# Power.net
KiCad netlist of a schematic drawn in Altium Designer
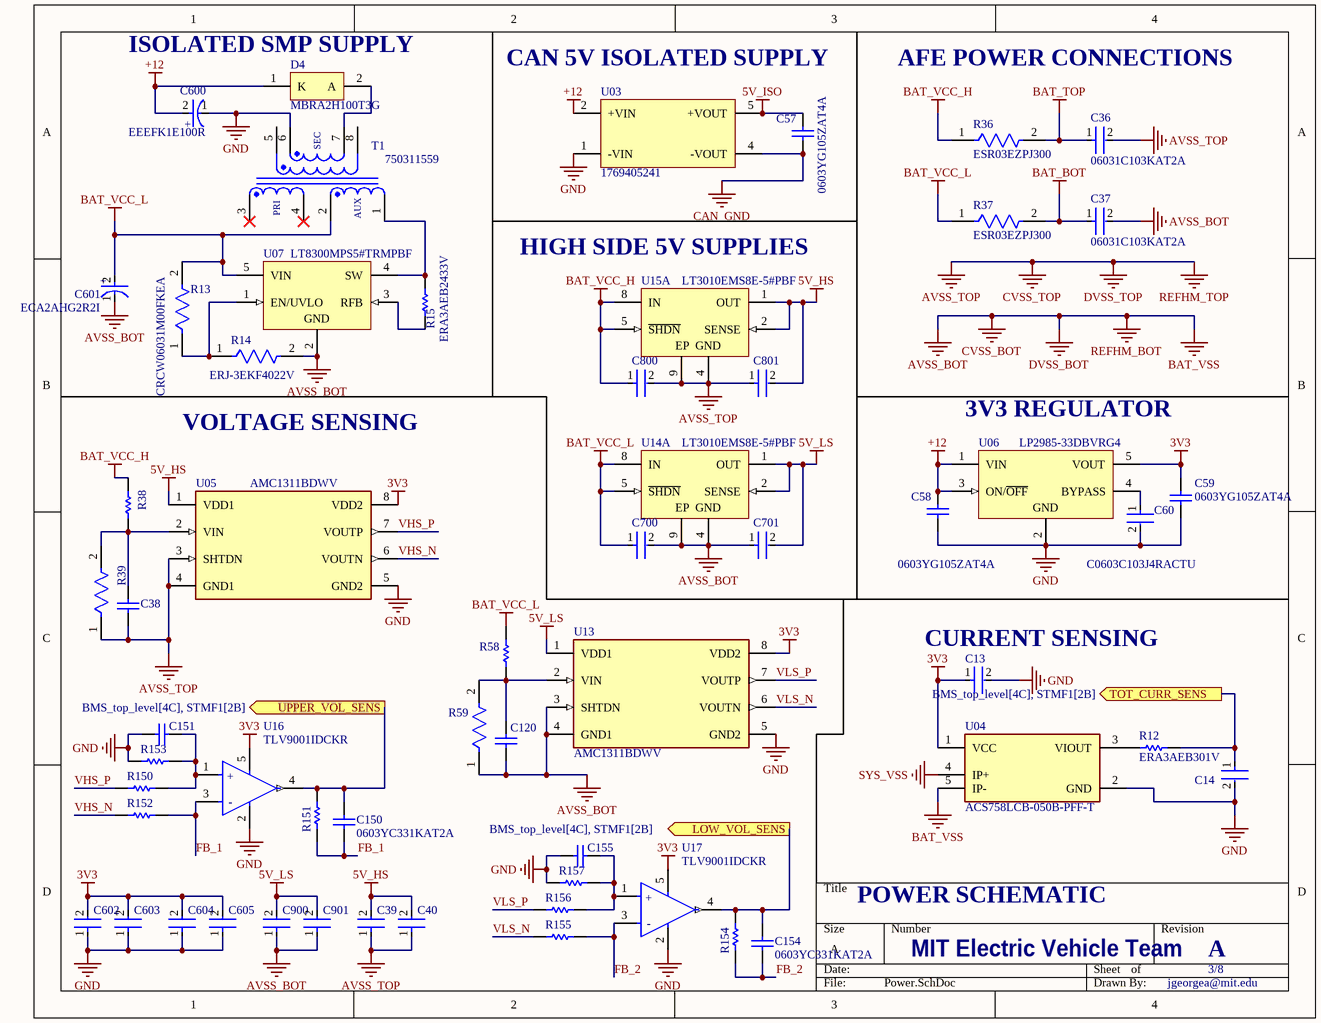
[diagram p0: Power.SchDoc]

(export (version "E")
  (design (tool "Eeschema 10.0.6"))
  (components
    (comp (ref "C13")
      (value "CGA3E2X7R1H104K080AA")
      (footprint "FP-CGA3E-0_3-0_1-IPC_A")
      (description "Cap Ceramic 100nF 50V X7R 10% Pad SMD 0603 +125°C Automotive T/R")
      (fields (field (name "TOLERANCE") "10%") (field (name "VOLTAGE") "50V"))
      (libsource (lib "Altium Content Vault") (part "b4654b650e69147ec39a6b967a45e02"))
    )
    (comp (ref "C14")
      (value "CGA3E2X7R1H104K080AA")
      (footprint "FP-CGA3E-0_3-0_1-IPC_A")
      (description "Cap Ceramic 100nF 50V X7R 10% Pad SMD 0603 +125°C Automotive T/R")
      (fields (field (name "TOLERANCE") "10%") (field (name "VOLTAGE") "50V"))
      (libsource (lib "Altium Content Vault") (part "b4654b650e69147ec39a6b967a45e02"))
    )
    (comp (ref "C36")
      (value "06031C103KAT2A")
      (footprint "FP-0603-L_1_6_0_15-W_0_81-IPC_C")
      (description "General Purpose Ceramic Capacitor, 0603, 10nF, 10%, X7R, 15%, 100V")
      (fields (field (name "VOLTAGE") "100V") (field (name "TOLERANCE") "10%"))
      (libsource (lib "Altium Content Vault") (part "02cd4be3c70576c341d710602a673aa"))
    )
    (comp (ref "C37")
      (value "06031C103KAT2A")
      (footprint "FP-0603-L_1_6_0_15-W_0_81-IPC_C")
      (description "General Purpose Ceramic Capacitor, 0603, 10nF, 10%, X7R, 15%, 100V")
      (fields (field (name "VOLTAGE") "100V") (field (name "TOLERANCE") "10%"))
      (libsource (lib "Altium Content Vault") (part "02cd4be3c70576c341d710602a673aa"))
    )
    (comp (ref "C38")
      (value "CC0603JRNPO9BN101")
      (footprint "CAPC1608X90X40ML10T20")
      (description "Chip Capacitor, 100 pF, +/- 5%, 50 V, -55 to 125 degC, 0603 (1608 Metric), RoHS, Tape and Reel")
      (fields (field (name "TOLERANCE") "5%") (field (name "VOLTAGE") "50V"))
      (libsource (lib "Altium Content Vault") (part "CAP-NP-2"))
    )
    (comp (ref "C39")
      (value "C2012X7S2A105K125AE")
      (footprint "FP-C2012-125-IPC_B")
      (description "CAP CER 1UF 100V X7S 0805")
      (fields (field (name "TOLERANCE") "10%"))
      (libsource (lib "Altium Content Vault") (part "02cd4be3c70576c341d710602a673aa"))
    )
    (comp (ref "C40")
      (value "CGA3E2X7R1H104K080AA")
      (footprint "FP-CGA3E-0_3-0_1-IPC_A")
      (description "Cap Ceramic 100nF 50V X7R 10% Pad SMD 0603 +125°C Automotive T/R")
      (fields (field (name "TOLERANCE") "10%") (field (name "VOLTAGE") "50V"))
      (libsource (lib "Altium Content Vault") (part "b4654b650e69147ec39a6b967a45e02"))
    )
    (comp (ref "C57")
      (value "0603YG105ZAT4A")
      (footprint "CAPC1608X90X35ML15T15")
      (fields (field (name "MANUFACTURER") "AVX Interconnect / Elco"))
      (libsource (lib "Altium Content Vault") (part "CAP"))
    )
    (comp (ref "C58")
      (value "0603YG105ZAT4A")
      (footprint "CAPC1608X90X35ML15T15")
      (fields (field (name "MANUFACTURER") "AVX Interconnect / Elco"))
      (libsource (lib "Altium Content Vault") (part "CAP"))
    )
    (comp (ref "C59")
      (value "0603YG105ZAT4A")
      (footprint "CAPC1608X90X35ML15T15")
      (fields (field (name "MANUFACTURER") "AVX Interconnect / Elco"))
      (libsource (lib "Altium Content Vault") (part "CAP"))
    )
    (comp (ref "C60")
      (value "C0603C103J4RACTU")
      (footprint "FP-C0603C-CF-MFG")
      (description "CAP CER 10000PF 16V 5% X7R 0603")
      (fields (field (name "TOLERANCE") "0.05") (field (name "MANUFACTURER") "KEMET"))
      (libsource (lib "Altium Content Vault") (part "b4654b650e69147ec39a6b967a45e02"))
    )
    (comp (ref "C120")
      (value "CC0603JRNPO9BN101")
      (footprint "CAPC1608X90X40ML10T20")
      (description "Chip Capacitor, 100 pF, +/- 5%, 50 V, -55 to 125 degC, 0603 (1608 Metric), RoHS, Tape and Reel")
      (fields (field (name "TOLERANCE") "5%") (field (name "VOLTAGE") "50V"))
      (libsource (lib "Altium Content Vault") (part "CAP-NP-2"))
    )
    (comp (ref "C150")
      (value "0603YC331KAT2A")
      (footprint "CAPC1608X90X35ML15T15")
      (fields (field (name "MANUFACTURER") "AVX Interconnect / Elco"))
      (libsource (lib "Altium Content Vault") (part "CAP"))
    )
    (comp (ref "C151")
      (value "0603YC331KAT2A")
      (footprint "CAPC1608X90X35ML15T15")
      (fields (field (name "MANUFACTURER") "AVX Interconnect / Elco"))
      (libsource (lib "Altium Content Vault") (part "CAP"))
    )
    (comp (ref "C154")
      (value "0603YC331KAT2A")
      (footprint "CAPC1608X90X35ML15T15")
      (fields (field (name "MANUFACTURER") "AVX Interconnect / Elco"))
      (libsource (lib "Altium Content Vault") (part "CAP"))
    )
    (comp (ref "C155")
      (value "0603YC331KAT2A")
      (footprint "CAPC1608X90X35ML15T15")
      (fields (field (name "MANUFACTURER") "AVX Interconnect / Elco"))
      (libsource (lib "Altium Content Vault") (part "CAP"))
    )
    (comp (ref "C600")
      (value "EEEFK1E100R")
      (footprint "FP-FKB-MFG")
      (description "CAP ALUM 10UF 20% 25V SMD")
      (fields (field (name "VOLTAGE") "25V") (field (name "TOLERANCE") "20%"))
      (libsource (lib "Altium Content Vault") (part "203bc49f2ac43e59fd269a8c329ed05"))
    )
    (comp (ref "C601")
      (value "ECA2AHG2R2I")
      (footprint "FP-RAD-TH-D_5_0_5-L_11_1-MFG")
      (description "Aluminum Electrolytic Capacitors (Radial Lead Type) AEC-Q200 Qualified 2.2uF ±20% 100V")
      (fields (field (name "TOLERANCE") "20%"))
      (libsource (lib "Altium Content Vault") (part "a00bbbee19879c290e62620ae7e47b1"))
    )
    (comp (ref "C602")
      (value "C2012X7S2A105K125AE")
      (footprint "FP-C2012-125-IPC_B")
      (description "CAP CER 1UF 100V X7S 0805")
      (fields (field (name "TOLERANCE") "10%"))
      (libsource (lib "Altium Content Vault") (part "02cd4be3c70576c341d710602a673aa"))
    )
    (comp (ref "C603")
      (value "C2012X7S2A105K125AE")
      (footprint "FP-C2012-125-IPC_B")
      (description "CAP CER 1UF 100V X7S 0805")
      (fields (field (name "TOLERANCE") "10%"))
      (libsource (lib "Altium Content Vault") (part "02cd4be3c70576c341d710602a673aa"))
    )
    (comp (ref "C604")
      (value "CGA3E2X7R1H104K080AA")
      (footprint "FP-CGA3E-0_3-0_1-IPC_A")
      (description "Cap Ceramic 100nF 50V X7R 10% Pad SMD 0603 +125°C Automotive T/R")
      (fields (field (name "TOLERANCE") "10%") (field (name "VOLTAGE") "50V"))
      (libsource (lib "Altium Content Vault") (part "b4654b650e69147ec39a6b967a45e02"))
    )
    (comp (ref "C605")
      (value "CGA3E2X7R1H104K080AA")
      (footprint "FP-CGA3E-0_3-0_1-IPC_A")
      (description "Cap Ceramic 100nF 50V X7R 10% Pad SMD 0603 +125°C Automotive T/R")
      (fields (field (name "TOLERANCE") "10%") (field (name "VOLTAGE") "50V"))
      (libsource (lib "Altium Content Vault") (part "b4654b650e69147ec39a6b967a45e02"))
    )
    (comp (ref "C700")
      (value "C2012X7S2A105K125AE")
      (footprint "FP-C2012-125-IPC_B")
      (description "CAP CER 1UF 100V X7S 0805")
      (fields (field (name "TOLERANCE") "10%"))
      (libsource (lib "Altium Content Vault") (part "02cd4be3c70576c341d710602a673aa"))
    )
    (comp (ref "C701")
      (value "C2012X7S2A105K125AE")
      (footprint "FP-C2012-125-IPC_B")
      (description "CAP CER 1UF 100V X7S 0805")
      (fields (field (name "TOLERANCE") "10%"))
      (libsource (lib "Altium Content Vault") (part "02cd4be3c70576c341d710602a673aa"))
    )
    (comp (ref "C800")
      (value "C2012X7S2A105K125AE")
      (footprint "FP-C2012-125-IPC_B")
      (description "CAP CER 1UF 100V X7S 0805")
      (fields (field (name "TOLERANCE") "10%"))
      (libsource (lib "Altium Content Vault") (part "02cd4be3c70576c341d710602a673aa"))
    )
    (comp (ref "C801")
      (value "C2012X7S2A105K125AE")
      (footprint "FP-C2012-125-IPC_B")
      (description "CAP CER 1UF 100V X7S 0805")
      (fields (field (name "TOLERANCE") "10%"))
      (libsource (lib "Altium Content Vault") (part "02cd4be3c70576c341d710602a673aa"))
    )
    (comp (ref "C900")
      (value "C2012X7S2A105K125AE")
      (footprint "FP-C2012-125-IPC_B")
      (description "CAP CER 1UF 100V X7S 0805")
      (fields (field (name "TOLERANCE") "10%"))
      (libsource (lib "Altium Content Vault") (part "02cd4be3c70576c341d710602a673aa"))
    )
    (comp (ref "C901")
      (value "CGA3E2X7R1H104K080AA")
      (footprint "FP-CGA3E-0_3-0_1-IPC_A")
      (description "Cap Ceramic 100nF 50V X7R 10% Pad SMD 0603 +125°C Automotive T/R")
      (fields (field (name "TOLERANCE") "10%") (field (name "VOLTAGE") "50V"))
      (libsource (lib "Altium Content Vault") (part "b4654b650e69147ec39a6b967a45e02"))
    )
    (comp (ref "D4")
      (value "MBRA2H100T3G")
      (footprint "ONSC-SMA-2-403D-02_V")
      (description "Schottky Power Rectifier, 2-Pin SMA, Pb-Free, Tape and Reel")
      (fields (field (name "MANUFACTURER") "On Semiconductor"))
      (libsource (lib "Altium Content Vault") (part "ONSC-D-K1A2-2_A"))
    )
    (comp (ref "R12")
      (value "ERA3AEB301V")
      (footprint "RESC1608X55X30LL20T20")
      (fields (field (name "MANUFACTURER") "Panasonic"))
      (libsource (lib "Altium Content Vault") (part "RES"))
    )
    (comp (ref "R13")
      (value "CRCW06031M00FKEA")
      (footprint "FP-CRCW0603-e3-MFG")
      (description "RES Thick Film, 1MΩ, 1%, 0.1W, 100ppm/°C, 0603")
      (fields (field (name "TOLERANCE") "1%"))
      (libsource (lib "Altium Content Vault") (part "1029c3af85768c4190bb7ad29bc67b5"))
    )
    (comp (ref "R14")
      (value "ERJ-3EKF4022V")
      (footprint "FP-ERJ3EK-IPC_C")
      (description "RES SMD 40.2K OHM 1% 1/10W 0603")
      (fields (field (name "TOLERANCE") "1%"))
      (libsource (lib "Altium Content Vault") (part "1029c3af85768c4190bb7ad29bc67b5"))
    )
    (comp (ref "R15")
      (value "ERA3AEB2433V")
      (footprint "RESC1608X55X30NL20T20")
      (fields (field (name "MANUFACTURER") "Panasonic"))
      (libsource (lib "Altium Content Vault") (part "RES"))
    )
    (comp (ref "R36")
      (value "ESR03EZPJ300")
      (footprint "FP-ESR03-MFG")
      (description "30Ω ±5% 0.25W 0603 Anti-Surge Chip Resistor AEC-Q200")
      (fields (field (name "TOLERANCE") "5%"))
      (libsource (lib "Altium Content Vault") (part "1029c3af85768c4190bb7ad29bc67b5"))
    )
    (comp (ref "R37")
      (value "ESR03EZPJ300")
      (footprint "FP-ESR03-MFG")
      (description "30Ω ±5% 0.25W 0603 Anti-Surge Chip Resistor AEC-Q200")
      (fields (field (name "TOLERANCE") "5%"))
      (libsource (lib "Altium Content Vault") (part "1029c3af85768c4190bb7ad29bc67b5"))
    )
    (comp (ref "R38")
      (value "ERJ-3GEYJ245V")
      (footprint "RESC1608X55X30ML15T15")
      (fields (field (name "MANUFACTURER") "Panasonic"))
      (libsource (lib "Altium Content Vault") (part "RES"))
    )
    (comp (ref "R39")
      (value "RT0603FRE0739K2L")
      (footprint "FP-RT0603-MFG")
      (description "RES SMD 39.2K OHM 1% 1/10W 0603")
      (fields (field (name "MANUFACTURER") "Yageo") (field (name "TOLERANCE") "0.01"))
      (libsource (lib "Altium Content Vault") (part "1029c3af85768c4190bb7ad29bc67b5"))
    )
    (comp (ref "R58")
      (value "ERJ-3GEYJ245V")
      (footprint "RESC1608X55X30ML15T15")
      (fields (field (name "MANUFACTURER") "Panasonic"))
      (libsource (lib "Altium Content Vault") (part "RES"))
    )
    (comp (ref "R59")
      (value "RT0603FRE0739K2L")
      (footprint "FP-RT0603-MFG")
      (description "RES SMD 39.2K OHM 1% 1/10W 0603")
      (fields (field (name "MANUFACTURER") "Yageo") (field (name "TOLERANCE") "0.01"))
      (libsource (lib "Altium Content Vault") (part "1029c3af85768c4190bb7ad29bc67b5"))
    )
    (comp (ref "R150")
      (value "ERJ-3EKF3301V")
      (footprint "RESC1609X55X30ML15T15")
      (description "Chip Resistors, 3.3 KOhm, +/- 1%, 0.1 W, 0603 (1608 Metric), -55 to 155 degC, RoHS, Tape and Reel")
      (fields (field (name "MANUFACTURER") "Panasonic") (field (name "TOLERANCE") "1%"))
      (libsource (lib "Altium Content Vault") (part "RES-2"))
    )
    (comp (ref "R151")
      (value "ERJ-3EKF3301V")
      (footprint "RESC1609X55X30ML15T15")
      (description "Chip Resistors, 3.3 KOhm, +/- 1%, 0.1 W, 0603 (1608 Metric), -55 to 155 degC, RoHS, Tape and Reel")
      (fields (field (name "MANUFACTURER") "Panasonic") (field (name "TOLERANCE") "1%"))
      (libsource (lib "Altium Content Vault") (part "RES-2"))
    )
    (comp (ref "R152")
      (value "ERJ-3EKF3301V")
      (footprint "RESC1609X55X30ML15T15")
      (description "Chip Resistors, 3.3 KOhm, +/- 1%, 0.1 W, 0603 (1608 Metric), -55 to 155 degC, RoHS, Tape and Reel")
      (fields (field (name "MANUFACTURER") "Panasonic") (field (name "TOLERANCE") "1%"))
      (libsource (lib "Altium Content Vault") (part "RES-2"))
    )
    (comp (ref "R153")
      (value "ERJ-3EKF3301V")
      (footprint "RESC1609X55X30ML15T15")
      (description "Chip Resistors, 3.3 KOhm, +/- 1%, 0.1 W, 0603 (1608 Metric), -55 to 155 degC, RoHS, Tape and Reel")
      (fields (field (name "MANUFACTURER") "Panasonic") (field (name "TOLERANCE") "1%"))
      (libsource (lib "Altium Content Vault") (part "RES-2"))
    )
    (comp (ref "R154")
      (value "ERJ-3EKF3301V")
      (footprint "RESC1609X55X30ML15T15")
      (description "Chip Resistors, 3.3 KOhm, +/- 1%, 0.1 W, 0603 (1608 Metric), -55 to 155 degC, RoHS, Tape and Reel")
      (fields (field (name "MANUFACTURER") "Panasonic") (field (name "TOLERANCE") "1%"))
      (libsource (lib "Altium Content Vault") (part "RES-2"))
    )
    (comp (ref "R155")
      (value "ERJ-3EKF3301V")
      (footprint "RESC1609X55X30ML15T15")
      (description "Chip Resistors, 3.3 KOhm, +/- 1%, 0.1 W, 0603 (1608 Metric), -55 to 155 degC, RoHS, Tape and Reel")
      (fields (field (name "MANUFACTURER") "Panasonic") (field (name "TOLERANCE") "1%"))
      (libsource (lib "Altium Content Vault") (part "RES-2"))
    )
    (comp (ref "R156")
      (value "ERJ-3EKF3301V")
      (footprint "RESC1609X55X30ML15T15")
      (description "Chip Resistors, 3.3 KOhm, +/- 1%, 0.1 W, 0603 (1608 Metric), -55 to 155 degC, RoHS, Tape and Reel")
      (fields (field (name "MANUFACTURER") "Panasonic") (field (name "TOLERANCE") "1%"))
      (libsource (lib "Altium Content Vault") (part "RES-2"))
    )
    (comp (ref "R157")
      (value "ERJ-3EKF3301V")
      (footprint "RESC1609X55X30ML15T15")
      (description "Chip Resistors, 3.3 KOhm, +/- 1%, 0.1 W, 0603 (1608 Metric), -55 to 155 degC, RoHS, Tape and Reel")
      (fields (field (name "MANUFACTURER") "Panasonic") (field (name "TOLERANCE") "1%"))
      (libsource (lib "Altium Content Vault") (part "RES-2"))
    )
    (comp (ref "T1")
      (value "750311559")
      (footprint "WE-FLYLT_EP7_L9.78W9.50H10.54")
      (libsource (lib "Altium Content Vault") (part "750311559"))
    )
    (comp (ref "U03")
      (value "1769405241")
      (footprint "WPME-FISM_SMT-8_L13.2W11.4H7.25")
      (description "1769405241 WPME-FISM Fixed Isolated SIP/SMT Module")
      (libsource (lib "Altium Content Vault") (part "SMT-8 - WPME-FISM"))
    )
    (comp (ref "U04")
      (value "ACS758LCB-050B-PFF-T")
      (footprint "FP-CB-5-PFF-MFG")
      (description "SENSOR CURRENT HALL 50A AC/DC")
      (libsource (lib "Altium Content Vault") (part "253ec7f09021dd5dcb901d30938890d"))
    )
    (comp (ref "U05")
      (value "AMC1311BDWV")
      (footprint "FP-DWV0008A-MFG")
      (description "IC ISOLATION 8SOIC")
      (fields
        (field (name "MANUFACTURER") "Texas Instruments")
        (field (name "OCTOPART") "https://octopart.com/amc1311bdwv-texas+instruments-88030782")
      )
      (libsource (lib "Altium Content Vault") (part "59c49c505aa37719ef898ce9673978d"))
    )
    (comp (ref "U06")
      (value "LP2985-33DBVRG4")
      (footprint "DBV0005A_M")
      (fields (field (name "MANUFACTURER") "Texas Instruments"))
      (libsource (lib "Altium Content Vault") (part "TI-LP2985_A-10DBV5"))
    )
    (comp (ref "U07")
      (value "LT8300MPS5#TRMPBF")
      (footprint "LT-S5-5-TSOT-23_N")
      (fields (field (name "MANUFACTURER") "Linear Technology"))
      (libsource (lib "Altium Content Vault") (part "LT-LT8300-S5-5"))
    )
    (comp (ref "U13")
      (value "AMC1311BDWV")
      (footprint "FP-DWV0008A-MFG")
      (description "IC ISOLATION 8SOIC")
      (fields
        (field (name "MANUFACTURER") "Texas Instruments")
        (field (name "OCTOPART") "https://octopart.com/amc1311bdwv-texas+instruments-88030782")
      )
      (libsource (lib "Altium Content Vault") (part "59c49c505aa37719ef898ce9673978d"))
    )
    (comp (ref "U14")
      (value "LT3010EMS8E-5#PBF")
      (footprint "LT-MS8E-8-1880X1680TP_L")
      (fields (field (name "MANUFACTURER") "Linear Technology"))
      (libsource (lib "Altium Content Vault") (part "LT-LT3010-5-MS8E-8"))
    )
    (comp (ref "U15")
      (value "LT3010EMS8E-5#PBF")
      (footprint "LT-MS8E-8-1880X1680TP_L")
      (fields (field (name "MANUFACTURER") "Linear Technology"))
      (libsource (lib "Altium Content Vault") (part "LT-LT3010-5-MS8E-8"))
    )
    (comp (ref "U16")
      (value "TLV9001IDCKR")
      (footprint "FP-DCK0005A-MFG")
      (description "IC CMOS 1 CIRCUIT SC70-5")
      (libsource (lib "Altium Content Vault") (part "471d8b929410cd356ad4b122f572ce5"))
    )
    (comp (ref "U17")
      (value "TLV9001IDCKR")
      (footprint "FP-DCK0005A-MFG")
      (description "IC CMOS 1 CIRCUIT SC70-5")
      (libsource (lib "Altium Content Vault") (part "471d8b929410cd356ad4b122f572ce5"))
    )
  )
  (nets
    (net (code "1") (name "+12") (class "Default")
      (node (ref "C58") (pin "2") (pinfunction "2_2") (pintype "passive"))
      (node (ref "C600") (pin "2") (pinfunction "A_2") (pintype "passive"))
      (node (ref "D4") (pin "1") (pinfunction "K_1") (pintype "passive"))
      (node (ref "U03") (pin "2") (pinfunction "+VIN_2") (pintype "passive"))
      (node (ref "U06") (pin "1") (pinfunction "VIN_1") (pintype "power_in"))
      (node (ref "U06") (pin "3") (pinfunction "ON/~{OFF}_3") (pintype "input"))
    )
    (net (code "2") (name "/FB_1") (class "Default")
      (node (ref "C150") (pin "1") (pinfunction "1_1") (pintype "passive"))
      (node (ref "R151") (pin "1") (pinfunction "1_1") (pintype "passive"))
      (node (ref "R152") (pin "1") (pinfunction "1_1") (pintype "passive"))
      (node (ref "U16") (pin "3") (pinfunction "IN-_3") (pintype "tri_state"))
    )
    (net (code "3") (name "/FB_2") (class "Default")
      (node (ref "C154") (pin "1") (pinfunction "1_1") (pintype "passive"))
      (node (ref "R154") (pin "1") (pinfunction "1_1") (pintype "passive"))
      (node (ref "R155") (pin "1") (pinfunction "1_1") (pintype "passive"))
      (node (ref "U17") (pin "3") (pinfunction "IN-_3") (pintype "tri_state"))
    )
    (net (code "4") (name "/LOW_VOL_SENS") (class "Default")
      (node (ref "C154") (pin "2") (pinfunction "2_2") (pintype "passive"))
      (node (ref "R154") (pin "2") (pinfunction "2_2") (pintype "passive"))
      (node (ref "U17") (pin "4") (pinfunction "OUT_4") (pintype "output"))
    )
    (net (code "5") (name "/TOT_CURR_SENS") (class "Default")
      (node (ref "C14") (pin "1") (pinfunction "1_1") (pintype "passive"))
      (node (ref "R12") (pin "2") (pinfunction "2_2") (pintype "passive"))
    )
    (net (code "6") (name "/UPPER_VOL_SENS") (class "Default")
      (node (ref "C150") (pin "2") (pinfunction "2_2") (pintype "passive"))
      (node (ref "R151") (pin "2") (pinfunction "2_2") (pintype "passive"))
      (node (ref "U16") (pin "4") (pinfunction "OUT_4") (pintype "output"))
    )
    (net (code "7") (name "/VHS_N") (class "Default")
      (node (ref "R152") (pin "2") (pinfunction "2_2") (pintype "passive"))
      (node (ref "U05") (pin "6") (pinfunction "VOUTN_6") (pintype "output"))
    )
    (net (code "8") (name "/VHS_P") (class "Default")
      (node (ref "R150") (pin "2") (pinfunction "2_2") (pintype "passive"))
      (node (ref "U05") (pin "7") (pinfunction "VOUTP_7") (pintype "output"))
    )
    (net (code "9") (name "/VLS_N") (class "Default")
      (node (ref "R155") (pin "2") (pinfunction "2_2") (pintype "passive"))
      (node (ref "U13") (pin "6") (pinfunction "VOUTN_6") (pintype "output"))
    )
    (net (code "10") (name "/VLS_P") (class "Default")
      (node (ref "R156") (pin "2") (pinfunction "2_2") (pintype "passive"))
      (node (ref "U13") (pin "7") (pinfunction "VOUTP_7") (pintype "output"))
    )
    (net (code "11") (name "3V3") (class "Default")
      (node (ref "C13") (pin "1") (pinfunction "1_1") (pintype "passive"))
      (node (ref "C59") (pin "2") (pinfunction "2_2") (pintype "passive"))
      (node (ref "C602") (pin "2") (pinfunction "2_2") (pintype "passive"))
      (node (ref "C603") (pin "2") (pinfunction "2_2") (pintype "passive"))
      (node (ref "C604") (pin "2") (pinfunction "2_2") (pintype "passive"))
      (node (ref "C605") (pin "2") (pinfunction "2_2") (pintype "passive"))
      (node (ref "U04") (pin "1") (pinfunction "VCC_1") (pintype "power_in"))
      (node (ref "U05") (pin "8") (pinfunction "VDD2_8") (pintype "power_in"))
      (node (ref "U06") (pin "5") (pinfunction "VOUT_5") (pintype "power_in"))
      (node (ref "U13") (pin "8") (pinfunction "VDD2_8") (pintype "power_in"))
      (node (ref "U16") (pin "5") (pinfunction "V+_5") (pintype "power_in"))
      (node (ref "U17") (pin "5") (pinfunction "V+_5") (pintype "power_in"))
    )
    (net (code "12") (name "5V_HS") (class "Default")
      (node (ref "C39") (pin "2") (pinfunction "2_2") (pintype "passive"))
      (node (ref "C40") (pin "2") (pinfunction "2_2") (pintype "passive"))
      (node (ref "C801") (pin "2") (pinfunction "2_2") (pintype "passive"))
      (node (ref "U05") (pin "1") (pinfunction "VDD1_1") (pintype "power_in"))
      (node (ref "U15") (pin "1") (pinfunction "OUT_1") (pintype "power_in"))
      (node (ref "U15") (pin "2") (pinfunction "SENSE_2") (pintype "input"))
    )
    (net (code "13") (name "5V_ISO") (class "Default")
      (node (ref "C57") (pin "2") (pinfunction "2_2") (pintype "passive"))
      (node (ref "U03") (pin "5") (pinfunction "+VOUT_5") (pintype "passive"))
    )
    (net (code "14") (name "5V_LS") (class "Default")
      (node (ref "C701") (pin "2") (pinfunction "2_2") (pintype "passive"))
      (node (ref "C900") (pin "2") (pinfunction "2_2") (pintype "passive"))
      (node (ref "C901") (pin "2") (pinfunction "2_2") (pintype "passive"))
      (node (ref "U13") (pin "1") (pinfunction "VDD1_1") (pintype "power_in"))
      (node (ref "U14") (pin "1") (pinfunction "OUT_1") (pintype "power_in"))
      (node (ref "U14") (pin "2") (pinfunction "SENSE_2") (pintype "input"))
    )
    (net (code "15") (name "AVSS_BOT") (class "Default")
      (node (ref "C120") (pin "1") (pinfunction "1_1") (pintype "passive"))
      (node (ref "C37") (pin "2") (pinfunction "2_2") (pintype "passive"))
      (node (ref "C601") (pin "1") (pinfunction "C_1") (pintype "passive"))
      (node (ref "C700") (pin "2") (pinfunction "2_2") (pintype "passive"))
      (node (ref "C701") (pin "1") (pinfunction "1_1") (pintype "passive"))
      (node (ref "C900") (pin "1") (pinfunction "1_1") (pintype "passive"))
      (node (ref "C901") (pin "1") (pinfunction "1_1") (pintype "passive"))
      (node (ref "R14") (pin "2") (pinfunction "2_2") (pintype "passive"))
      (node (ref "R59") (pin "1") (pinfunction "1_1") (pintype "passive"))
      (node (ref "U04") (pin "5") (pinfunction "IP-_5") (pintype "passive"))
      (node (ref "U07") (pin "2") (pinfunction "GND_2") (pintype "power_in"))
      (node (ref "U13") (pin "3") (pinfunction "SHTDN_3") (pintype "input"))
      (node (ref "U13") (pin "4") (pinfunction "GND1_4") (pintype "power_in"))
      (node (ref "U14") (pin "4") (pinfunction "GND_4") (pintype "power_in"))
      (node (ref "U14") (pin "9") (pinfunction "EP_9") (pintype "power_in"))
    )
    (net (code "16") (name "AVSS_TOP") (class "Default")
      (node (ref "C36") (pin "2") (pinfunction "2_2") (pintype "passive"))
      (node (ref "C38") (pin "1") (pinfunction "1_1") (pintype "passive"))
      (node (ref "C39") (pin "1") (pinfunction "1_1") (pintype "passive"))
      (node (ref "C40") (pin "1") (pinfunction "1_1") (pintype "passive"))
      (node (ref "C800") (pin "2") (pinfunction "2_2") (pintype "passive"))
      (node (ref "C801") (pin "1") (pinfunction "1_1") (pintype "passive"))
      (node (ref "R39") (pin "1") (pinfunction "1_1") (pintype "passive"))
      (node (ref "U05") (pin "3") (pinfunction "SHTDN_3") (pintype "input"))
      (node (ref "U05") (pin "4") (pinfunction "GND1_4") (pintype "power_in"))
      (node (ref "U15") (pin "4") (pinfunction "GND_4") (pintype "power_in"))
      (node (ref "U15") (pin "9") (pinfunction "EP_9") (pintype "power_in"))
    )
    (net (code "17") (name "BAT_BOT") (class "Default")
      (node (ref "C37") (pin "1") (pinfunction "1_1") (pintype "passive"))
      (node (ref "R37") (pin "2") (pinfunction "2_2") (pintype "passive"))
    )
    (net (code "18") (name "BAT_TOP") (class "Default")
      (node (ref "C36") (pin "1") (pinfunction "1_1") (pintype "passive"))
      (node (ref "R36") (pin "2") (pinfunction "2_2") (pintype "passive"))
    )
    (net (code "19") (name "BAT_VCC_H") (class "Default")
      (node (ref "C800") (pin "1") (pinfunction "1_1") (pintype "passive"))
      (node (ref "R36") (pin "1") (pinfunction "1_1") (pintype "passive"))
      (node (ref "R38") (pin "2") (pinfunction "2_2") (pintype "passive"))
      (node (ref "U15") (pin "5") (pinfunction "~{SHDN}_5") (pintype "input"))
      (node (ref "U15") (pin "8") (pinfunction "IN_8") (pintype "power_in"))
    )
    (net (code "20") (name "BAT_VCC_L") (class "Default")
      (node (ref "C601") (pin "2") (pinfunction "A_2") (pintype "passive"))
      (node (ref "C700") (pin "1") (pinfunction "1_1") (pintype "passive"))
      (node (ref "R13") (pin "2") (pinfunction "2_2") (pintype "passive"))
      (node (ref "R37") (pin "1") (pinfunction "1_1") (pintype "passive"))
      (node (ref "R58") (pin "2") (pinfunction "2_2") (pintype "passive"))
      (node (ref "T1") (pin "2") (pinfunction "2_2") (pintype "passive"))
      (node (ref "U07") (pin "5") (pinfunction "VIN_5") (pintype "power_in"))
      (node (ref "U14") (pin "5") (pinfunction "~{SHDN}_5") (pintype "input"))
      (node (ref "U14") (pin "8") (pinfunction "IN_8") (pintype "power_in"))
    )
    (net (code "21") (name "CAN_GND") (class "Default")
      (node (ref "C57") (pin "1") (pinfunction "1_1") (pintype "passive"))
      (node (ref "U03") (pin "4") (pinfunction "-VOUT_4") (pintype "passive"))
    )
    (net (code "22") (name "GND") (class "Default")
      (node (ref "C13") (pin "2") (pinfunction "2_2") (pintype "passive"))
      (node (ref "C14") (pin "2") (pinfunction "2_2") (pintype "passive"))
      (node (ref "C151") (pin "1") (pinfunction "1_1") (pintype "passive"))
      (node (ref "C155") (pin "1") (pinfunction "1_1") (pintype "passive"))
      (node (ref "C58") (pin "1") (pinfunction "1_1") (pintype "passive"))
      (node (ref "C59") (pin "1") (pinfunction "1_1") (pintype "passive"))
      (node (ref "C60") (pin "2") (pinfunction "2_2") (pintype "passive"))
      (node (ref "C600") (pin "1") (pinfunction "C_1") (pintype "passive"))
      (node (ref "C602") (pin "1") (pinfunction "1_1") (pintype "passive"))
      (node (ref "C603") (pin "1") (pinfunction "1_1") (pintype "passive"))
      (node (ref "C604") (pin "1") (pinfunction "1_1") (pintype "passive"))
      (node (ref "C605") (pin "1") (pinfunction "1_1") (pintype "passive"))
      (node (ref "R153") (pin "2") (pinfunction "2_2") (pintype "passive"))
      (node (ref "R157") (pin "2") (pinfunction "2_2") (pintype "passive"))
      (node (ref "T1") (pin "6") (pinfunction "6_6") (pintype "passive"))
      (node (ref "U03") (pin "1") (pinfunction "-VIN_1") (pintype "passive"))
      (node (ref "U04") (pin "2") (pinfunction "GND_2") (pintype "power_in"))
      (node (ref "U05") (pin "5") (pinfunction "GND2_5") (pintype "power_in"))
      (node (ref "U06") (pin "2") (pinfunction "GND_2") (pintype "power_in"))
      (node (ref "U13") (pin "5") (pinfunction "GND2_5") (pintype "power_in"))
      (node (ref "U16") (pin "2") (pinfunction "V-_2") (pintype "power_in"))
      (node (ref "U17") (pin "2") (pinfunction "V-_2") (pintype "power_in"))
    )
    (net (code "23") (name "Net-(D4-A)") (class "Default")
      (node (ref "D4") (pin "2") (pinfunction "A_2") (pintype "passive"))
      (node (ref "T1") (pin "7") (pinfunction "7_7") (pintype "passive"))
    )
    (net (code "24") (name "Net-(U04-VIOUT)") (class "Default")
      (node (ref "R12") (pin "1") (pinfunction "1_1") (pintype "passive"))
      (node (ref "U04") (pin "3") (pinfunction "VIOUT_3") (pintype "passive"))
    )
    (net (code "25") (name "Net-(U05-VIN)") (class "Default")
      (node (ref "C38") (pin "2") (pinfunction "2_2") (pintype "passive"))
      (node (ref "R38") (pin "1") (pinfunction "1_1") (pintype "passive"))
      (node (ref "R39") (pin "2") (pinfunction "2_2") (pintype "passive"))
      (node (ref "U05") (pin "2") (pinfunction "VIN_2") (pintype "input"))
    )
    (net (code "26") (name "Net-(U06-BYPASS)") (class "Default")
      (node (ref "C60") (pin "1") (pinfunction "1_1") (pintype "passive"))
      (node (ref "U06") (pin "4") (pinfunction "BYPASS_4") (pintype "passive"))
    )
    (net (code "27") (name "Net-(U07-EN{slash}UVLO)") (class "Default")
      (node (ref "R13") (pin "1") (pinfunction "1_1") (pintype "passive"))
      (node (ref "R14") (pin "1") (pinfunction "1_1") (pintype "passive"))
      (node (ref "U07") (pin "1") (pinfunction "EN/UVLO_1") (pintype "input"))
    )
    (net (code "28") (name "Net-(U07-RFB)") (class "Default")
      (node (ref "R15") (pin "1") (pinfunction "1_1") (pintype "passive"))
      (node (ref "U07") (pin "3") (pinfunction "RFB_3") (pintype "input"))
    )
    (net (code "29") (name "Net-(U07-SW)") (class "Default")
      (node (ref "R15") (pin "2") (pinfunction "2_2") (pintype "passive"))
      (node (ref "T1") (pin "1") (pinfunction "1_1") (pintype "passive"))
      (node (ref "U07") (pin "4") (pinfunction "SW_4") (pintype "power_in"))
    )
    (net (code "30") (name "Net-(U13-VIN)") (class "Default")
      (node (ref "C120") (pin "2") (pinfunction "2_2") (pintype "passive"))
      (node (ref "R58") (pin "1") (pinfunction "1_1") (pintype "passive"))
      (node (ref "R59") (pin "2") (pinfunction "2_2") (pintype "passive"))
      (node (ref "U13") (pin "2") (pinfunction "VIN_2") (pintype "input"))
    )
    (net (code "31") (name "Net-(U16-IN+)") (class "Default")
      (node (ref "C151") (pin "2") (pinfunction "2_2") (pintype "passive"))
      (node (ref "R150") (pin "1") (pinfunction "1_1") (pintype "passive"))
      (node (ref "R153") (pin "1") (pinfunction "1_1") (pintype "passive"))
      (node (ref "U16") (pin "1") (pinfunction "IN+_1") (pintype "tri_state"))
    )
    (net (code "32") (name "Net-(U17-IN+)") (class "Default")
      (node (ref "C155") (pin "2") (pinfunction "2_2") (pintype "passive"))
      (node (ref "R156") (pin "1") (pinfunction "1_1") (pintype "passive"))
      (node (ref "R157") (pin "1") (pinfunction "1_1") (pintype "passive"))
      (node (ref "U17") (pin "1") (pinfunction "IN+_1") (pintype "tri_state"))
    )
    (net (code "33") (name "SYS_VSS") (class "Default")
      (node (ref "U04") (pin "4") (pinfunction "IP+_4") (pintype "passive"))
    )
    (net (code "34") (name "unconnected-(T1-Pad3)") (class "Default")
      (node (ref "T1") (pin "3") (pinfunction "3_3") (pintype "passive+no_connect"))
    )
    (net (code "35") (name "unconnected-(T1-Pad4)") (class "Default")
      (node (ref "T1") (pin "4") (pinfunction "4_4") (pintype "passive+no_connect"))
    )
    (net (code "36") (name "unconnected-(T1-Pad5)") (class "Default")
      (node (ref "T1") (pin "5") (pinfunction "5_5") (pintype "passive"))
    )
    (net (code "37") (name "unconnected-(T1-Pad8)") (class "Default")
      (node (ref "T1") (pin "8") (pinfunction "8_8") (pintype "passive"))
    )
  )
)
